# SCH_steren_mot-300_water_pump_conmutatio.net
KiCad netlist of a schematic drawn in EasyEDA
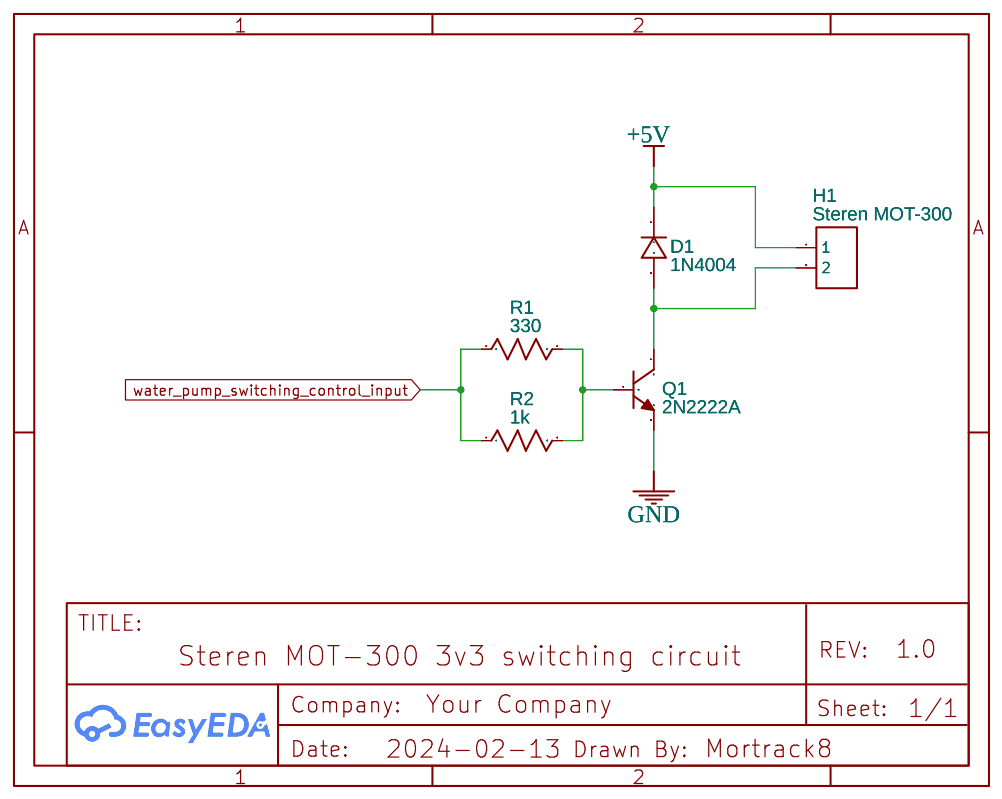
[diagram p0: template_circuit]
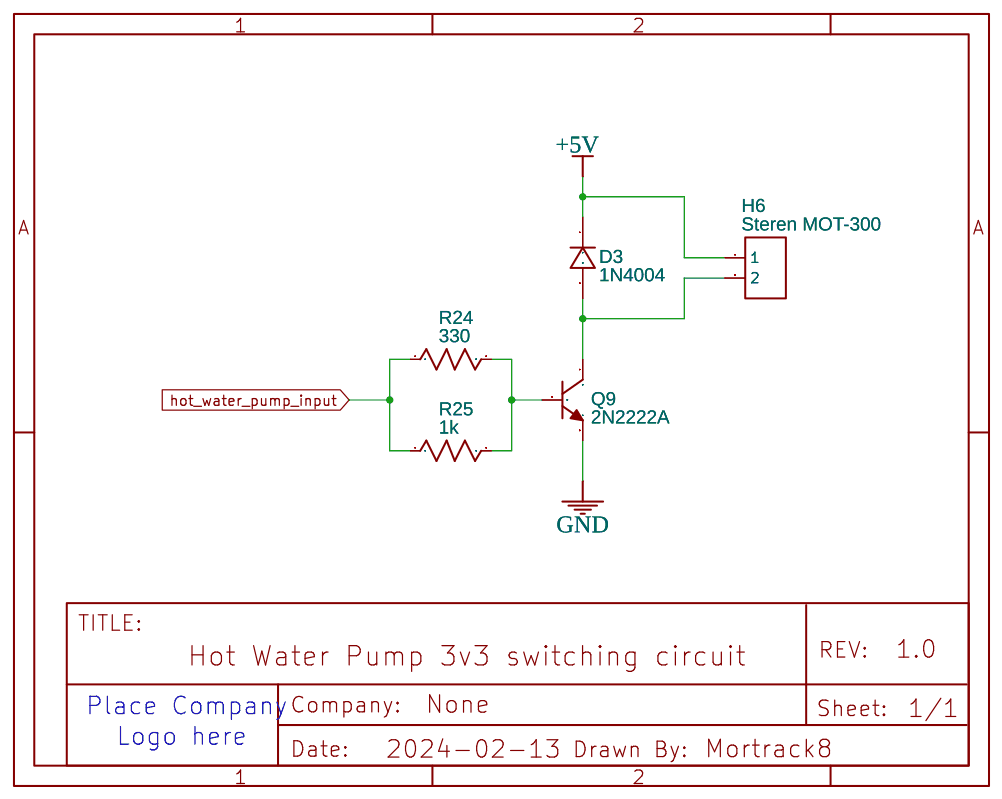
[diagram p1: hot_water_pump_3v3_switching_circuit]
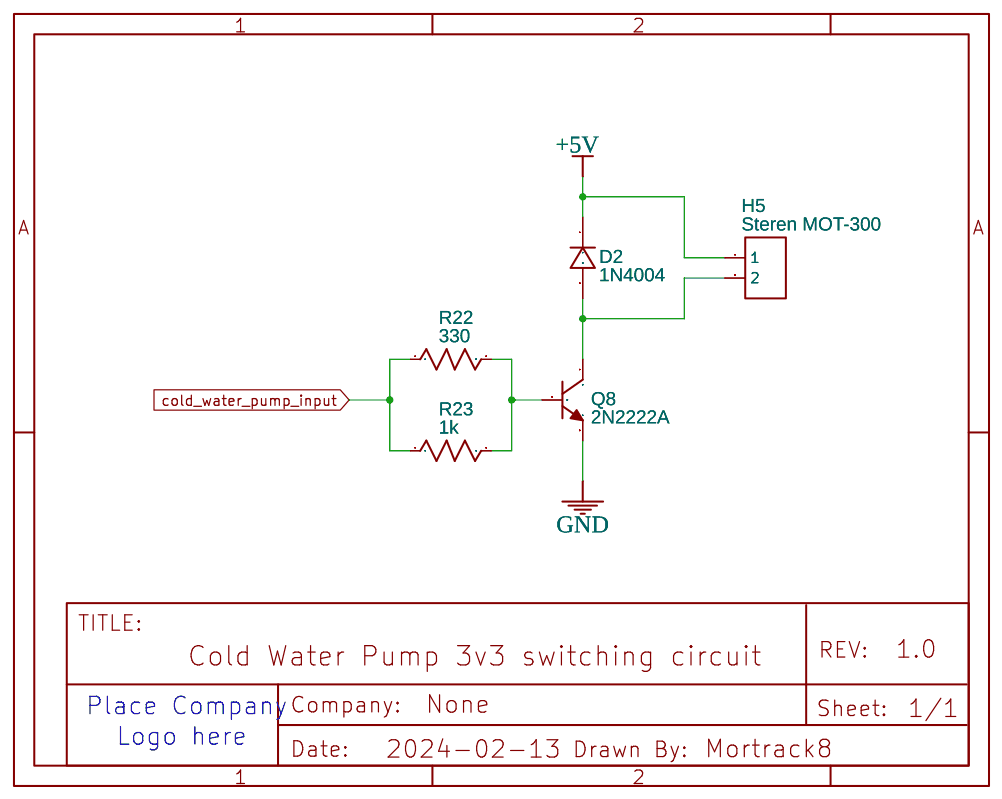
[diagram p2: cold_water_pump_3v3_switching_circuit]

(export (version "E")
  (design (tool "Eeschema 10.0.6"))
  (components
    (comp (ref "D1")
      (value "1N4004")
      (fields (field (name "Manufacturer Part") "1N4004G") (field (name "Manufacturer") "onsemi(安森美)"))
      (libsource (lib "") (part "1N4004G"))
    )
    (comp (ref "H1") (value "Steren MOT-300") (libsource (lib "") (part "HDR-F-2.54_1x2")))
    (comp (ref "Q1")
      (value "2N2222A")
      (fields (field (name "Manufacturer") "BLUE ROCKET(蓝箭)"))
      (libsource (lib "") (part "2N2222A"))
    )
    (comp (ref "R1") (value "330") (libsource (lib "") (part "R_AXIAL-0.5_US")))
    (comp (ref "R2") (value "1k") (libsource (lib "") (part "R_AXIAL-0.5_US")))
    (comp (ref "D3")
      (value "1N4004")
      (fields (field (name "Manufacturer Part") "1N4004G") (field (name "Manufacturer") "onsemi(安森美)"))
      (libsource (lib "") (part "1N4004G"))
    )
    (comp (ref "H6") (value "Steren MOT-300") (libsource (lib "") (part "HDR-F-2.54_1x2")))
    (comp (ref "Q9")
      (value "2N2222A")
      (fields (field (name "Manufacturer") "BLUE ROCKET(蓝箭)"))
      (libsource (lib "") (part "2N2222A"))
    )
    (comp (ref "R24") (value "330") (libsource (lib "") (part "R_AXIAL-0.5_US")))
    (comp (ref "R25") (value "1k") (libsource (lib "") (part "R_AXIAL-0.5_US")))
    (comp (ref "D2")
      (value "1N4004")
      (fields (field (name "Manufacturer Part") "1N4004G") (field (name "Manufacturer") "onsemi(安森美)"))
      (libsource (lib "") (part "1N4004G"))
    )
    (comp (ref "H5") (value "Steren MOT-300") (libsource (lib "") (part "HDR-F-2.54_1x2")))
    (comp (ref "Q8")
      (value "2N2222A")
      (fields (field (name "Manufacturer") "BLUE ROCKET(蓝箭)"))
      (libsource (lib "") (part "2N2222A"))
    )
    (comp (ref "R22") (value "330") (libsource (lib "") (part "R_AXIAL-0.5_US")))
    (comp (ref "R23") (value "1k") (libsource (lib "") (part "R_AXIAL-0.5_US")))
  )
  (nets
    (net (code "1") (name "+5V") (class "Default")
      (node (ref "D1") (pin "1") (pinfunction "1_1") (pintype "unspecified"))
      (node (ref "D2") (pin "1") (pinfunction "1_1") (pintype "unspecified"))
      (node (ref "D3") (pin "1") (pinfunction "1_1") (pintype "unspecified"))
      (node (ref "H1") (pin "1") (pinfunction "1_1") (pintype "input"))
      (node (ref "H5") (pin "1") (pinfunction "1_1") (pintype "input"))
      (node (ref "H6") (pin "1") (pinfunction "1_1") (pintype "input"))
    )
    (net (code "2") (name "GND") (class "Default")
      (node (ref "Q1") (pin "3") (pinfunction "E_3") (pintype "unspecified"))
      (node (ref "Q8") (pin "3") (pinfunction "E_3") (pintype "unspecified"))
      (node (ref "Q9") (pin "3") (pinfunction "E_3") (pintype "unspecified"))
    )
    (net (code "3") (name "Net-(Q1-B)") (class "Default")
      (node (ref "Q1") (pin "2") (pinfunction "B_2") (pintype "unspecified"))
      (node (ref "R1") (pin "2") (pinfunction "2_2") (pintype "unspecified"))
      (node (ref "R2") (pin "2") (pinfunction "2_2") (pintype "unspecified"))
    )
    (net (code "4") (name "Net-(Q1-C)") (class "Default")
      (node (ref "D1") (pin "2") (pinfunction "2_2") (pintype "unspecified"))
      (node (ref "H1") (pin "2") (pinfunction "2_2") (pintype "input"))
      (node (ref "Q1") (pin "1") (pinfunction "C_1") (pintype "unspecified"))
    )
    (net (code "5") (name "Net-(Q8-B)") (class "Default")
      (node (ref "Q8") (pin "2") (pinfunction "B_2") (pintype "unspecified"))
      (node (ref "R22") (pin "2") (pinfunction "2_2") (pintype "unspecified"))
      (node (ref "R23") (pin "2") (pinfunction "2_2") (pintype "unspecified"))
    )
    (net (code "6") (name "Net-(Q8-C)") (class "Default")
      (node (ref "D2") (pin "2") (pinfunction "2_2") (pintype "unspecified"))
      (node (ref "H5") (pin "2") (pinfunction "2_2") (pintype "input"))
      (node (ref "Q8") (pin "1") (pinfunction "C_1") (pintype "unspecified"))
    )
    (net (code "7") (name "Net-(Q9-B)") (class "Default")
      (node (ref "Q9") (pin "2") (pinfunction "B_2") (pintype "unspecified"))
      (node (ref "R24") (pin "2") (pinfunction "2_2") (pintype "unspecified"))
      (node (ref "R25") (pin "2") (pinfunction "2_2") (pintype "unspecified"))
    )
    (net (code "8") (name "Net-(Q9-C)") (class "Default")
      (node (ref "D3") (pin "2") (pinfunction "2_2") (pintype "unspecified"))
      (node (ref "H6") (pin "2") (pinfunction "2_2") (pintype "input"))
      (node (ref "Q9") (pin "1") (pinfunction "C_1") (pintype "unspecified"))
    )
    (net (code "9") (name "cold_water_pump_input") (class "Default")
      (node (ref "R22") (pin "1") (pinfunction "1_1") (pintype "unspecified"))
      (node (ref "R23") (pin "1") (pinfunction "1_1") (pintype "unspecified"))
    )
    (net (code "10") (name "hot_water_pump_input") (class "Default")
      (node (ref "R24") (pin "1") (pinfunction "1_1") (pintype "unspecified"))
      (node (ref "R25") (pin "1") (pinfunction "1_1") (pintype "unspecified"))
    )
    (net (code "11") (name "water_pump_switching_control_input") (class "Default")
      (node (ref "R1") (pin "1") (pinfunction "1_1") (pintype "unspecified"))
      (node (ref "R2") (pin "1") (pinfunction "1_1") (pintype "unspecified"))
    )
  )
)
